# ATmega64M1_Dev_Board.net
KiCad netlist of a schematic drawn in EAGLE
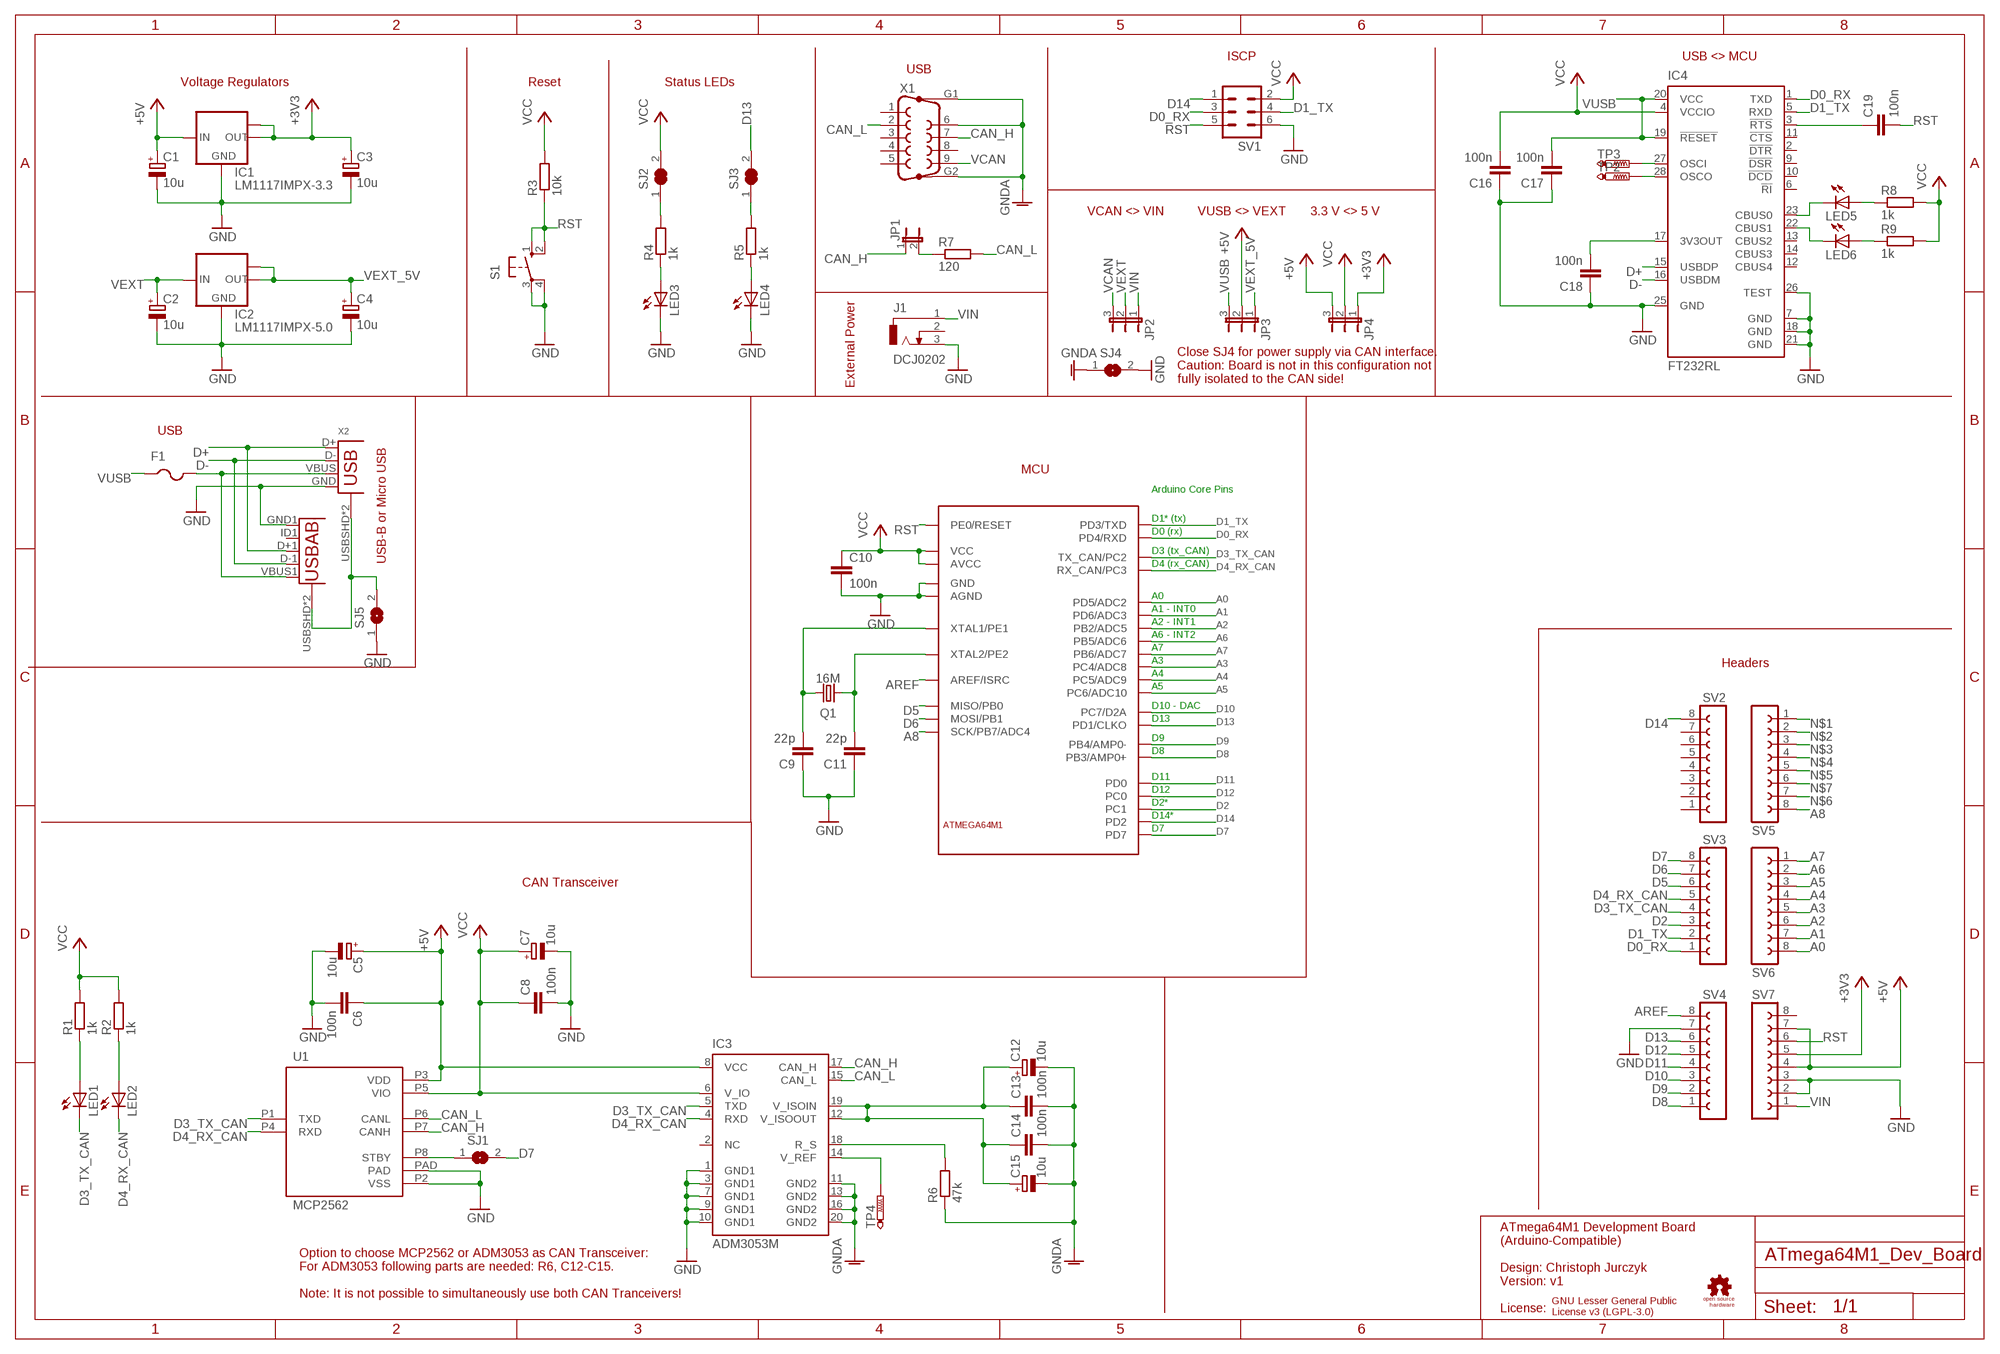
[diagram p0: schematic, sheet 1]

(export (version "E")
  (design (tool "Eeschema 10.0.6"))
  (components
    (comp (ref "C1")
      (value "10u")
      (footprint "eagle-import:A_3216-18W")
      (libsource (lib "eagle-import") (part "CPOL-EUA/3216-18W"))
    )
    (comp (ref "C2")
      (value "10u")
      (footprint "eagle-import:A_3216-18W")
      (libsource (lib "eagle-import") (part "CPOL-EUA/3216-18W"))
    )
    (comp (ref "C3")
      (value "10u")
      (footprint "eagle-import:A_3216-18W")
      (libsource (lib "eagle-import") (part "CPOL-EUA/3216-18W"))
    )
    (comp (ref "C4")
      (value "10u")
      (footprint "eagle-import:A_3216-18W")
      (libsource (lib "eagle-import") (part "CPOL-EUA/3216-18W"))
    )
    (comp (ref "C5")
      (value "10u")
      (footprint "eagle-import:A_3216-18W")
      (libsource (lib "eagle-import") (part "CPOL-EUA/3216-18W"))
    )
    (comp (ref "C6")
      (value "100n")
      (footprint "eagle-import:C0603")
      (libsource (lib "eagle-import") (part "C-EUC0603"))
    )
    (comp (ref "C7")
      (value "10u")
      (footprint "eagle-import:A_3216-18W")
      (libsource (lib "eagle-import") (part "CPOL-EUA/3216-18W"))
    )
    (comp (ref "C8")
      (value "100n")
      (footprint "eagle-import:C0603")
      (libsource (lib "eagle-import") (part "C-EUC0603"))
    )
    (comp (ref "C9")
      (value "22p")
      (footprint "eagle-import:C0603")
      (libsource (lib "eagle-import") (part "C-EUC0603"))
    )
    (comp (ref "C10")
      (value "100n")
      (footprint "eagle-import:C0603")
      (libsource (lib "eagle-import") (part "C-EUC0603"))
    )
    (comp (ref "C11")
      (value "22p")
      (footprint "eagle-import:C0603")
      (libsource (lib "eagle-import") (part "C-EUC0603"))
    )
    (comp (ref "C12")
      (value "10u")
      (footprint "eagle-import:A_3216-18W")
      (libsource (lib "eagle-import") (part "CPOL-EUA/3216-18W"))
    )
    (comp (ref "C13")
      (value "100n")
      (footprint "eagle-import:C0603")
      (libsource (lib "eagle-import") (part "C-EUC0603"))
    )
    (comp (ref "C14")
      (value "100n")
      (footprint "eagle-import:C0603")
      (libsource (lib "eagle-import") (part "C-EUC0603"))
    )
    (comp (ref "C15")
      (value "10u")
      (footprint "eagle-import:A_3216-18W")
      (libsource (lib "eagle-import") (part "CPOL-EUA/3216-18W"))
    )
    (comp (ref "C16")
      (value "100n")
      (footprint "eagle-import:C0603")
      (libsource (lib "eagle-import") (part "C-EUC0603"))
    )
    (comp (ref "C17")
      (value "100n")
      (footprint "eagle-import:C0603")
      (libsource (lib "eagle-import") (part "C-EUC0603"))
    )
    (comp (ref "C18")
      (value "100n")
      (footprint "eagle-import:C0603")
      (libsource (lib "eagle-import") (part "C-EUC0603"))
    )
    (comp (ref "C19")
      (value "100n")
      (footprint "eagle-import:C0603")
      (libsource (lib "eagle-import") (part "C-EUC0603"))
    )
    (comp (ref "F1")
      (value "PTCFUSE-1206")
      (footprint "eagle-import:R1206")
      (libsource (lib "eagle-import") (part "PTCFUSE-1206"))
    )
    (comp (ref "GOLD_ORB_SM1")
      (value "OSHWLOGOLOGO8MM")
      (footprint "eagle-import:OSHW_8MM")
      (libsource (lib "eagle-import") (part "OSHWLOGOLOGO8MM"))
    )
    (comp (ref "IC1")
      (value "LM1117IMPX-3.3")
      (footprint "eagle-import:SOT223")
      (libsource (lib "eagle-import") (part "LM1117IMPX-3.3"))
    )
    (comp (ref "IC2")
      (value "LM1117IMPX-5.0")
      (footprint "eagle-import:SOT223")
      (libsource (lib "eagle-import") (part "LM1117IMPX-5.0"))
    )
    (comp (ref "IC3")
      (value "ADM3053M")
      (footprint "eagle-import:SO20W")
      (libsource (lib "eagle-import") (part "ADM3053M"))
    )
    (comp (ref "IC4")
      (value "FT232RL")
      (footprint "eagle-import:SSOP28")
      (libsource (lib "eagle-import") (part "FT232RL"))
    )
    (comp (ref "IC11")
      (value "ATMEGA64M1TQFP32")
      (footprint "eagle-import:QFP-32")
      (libsource (lib "eagle-import") (part "ATMEGA64M1TQFP32"))
    )
    (comp (ref "J1")
      (value "DCJ0202")
      (footprint "eagle-import:DCJ0202")
      (libsource (lib "eagle-import") (part "DCJ0202"))
    )
    (comp (ref "JP1")
      (value "JP1E")
      (footprint "eagle-import:JP1")
      (libsource (lib "eagle-import") (part "JP1E"))
    )
    (comp (ref "JP2")
      (value "JP2E")
      (footprint "eagle-import:JP2")
      (libsource (lib "eagle-import") (part "JP2E"))
    )
    (comp (ref "JP3")
      (value "JP2E")
      (footprint "eagle-import:JP2")
      (libsource (lib "eagle-import") (part "JP2E"))
    )
    (comp (ref "JP4")
      (value "JP2E")
      (footprint "eagle-import:JP2")
      (libsource (lib "eagle-import") (part "JP2E"))
    )
    (comp (ref "LED1")
      (value "LEDSML0805")
      (footprint "eagle-import:SML0805")
      (libsource (lib "eagle-import") (part "LEDSML0805"))
    )
    (comp (ref "LED2")
      (value "LEDSML0805")
      (footprint "eagle-import:SML0805")
      (libsource (lib "eagle-import") (part "LEDSML0805"))
    )
    (comp (ref "LED3")
      (value "LEDSML0805")
      (footprint "eagle-import:SML0805")
      (libsource (lib "eagle-import") (part "LEDSML0805"))
    )
    (comp (ref "LED4")
      (value "LEDSML0805")
      (footprint "eagle-import:SML0805")
      (libsource (lib "eagle-import") (part "LEDSML0805"))
    )
    (comp (ref "LED5")
      (value "LEDSML0805")
      (footprint "eagle-import:SML0805")
      (libsource (lib "eagle-import") (part "LEDSML0805"))
    )
    (comp (ref "LED6")
      (value "LEDSML0805")
      (footprint "eagle-import:SML0805")
      (libsource (lib "eagle-import") (part "LEDSML0805"))
    )
    (comp (ref "Q1")
      (value "16M")
      (footprint "eagle-import:HC49_S")
      (libsource (lib "eagle-import") (part "CRYSTALHC49S"))
    )
    (comp (ref "R1")
      (value "1k")
      (footprint "eagle-import:M0805")
      (libsource (lib "eagle-import") (part "R-EU_M0805"))
    )
    (comp (ref "R2")
      (value "1k")
      (footprint "eagle-import:M0805")
      (libsource (lib "eagle-import") (part "R-EU_M0805"))
    )
    (comp (ref "R3")
      (value "10k")
      (footprint "eagle-import:M0805")
      (libsource (lib "eagle-import") (part "R-EU_M0805"))
    )
    (comp (ref "R4")
      (value "1k")
      (footprint "eagle-import:M0805")
      (libsource (lib "eagle-import") (part "R-EU_M0805"))
    )
    (comp (ref "R5")
      (value "1k")
      (footprint "eagle-import:M0805")
      (libsource (lib "eagle-import") (part "R-EU_M0805"))
    )
    (comp (ref "R6")
      (value "47k")
      (footprint "eagle-import:M0805")
      (libsource (lib "eagle-import") (part "R-EU_M0805"))
    )
    (comp (ref "R7")
      (value "120")
      (footprint "eagle-import:M0805")
      (libsource (lib "eagle-import") (part "R-EU_M0805"))
    )
    (comp (ref "R8")
      (value "1k")
      (footprint "eagle-import:M0805")
      (libsource (lib "eagle-import") (part "R-EU_M0805"))
    )
    (comp (ref "R9")
      (value "1k")
      (footprint "eagle-import:M0805")
      (libsource (lib "eagle-import") (part "R-EU_M0805"))
    )
    (comp (ref "S1")
      (value "10-XX")
      (footprint "eagle-import:B3F-10XX")
      (fields (field (name "MPN") "B3F-1000"))
      (libsource (lib "eagle-import") (part "10-XX"))
    )
    (comp (ref "SJ1") (value "SJ") (footprint "eagle-import:SJ") (libsource (lib "eagle-import") (part "SJ")))
    (comp (ref "SJ2")
      (value "SJ_NC")
      (footprint "eagle-import:SJ_NC")
      (libsource (lib "eagle-import") (part "SJ_NC"))
    )
    (comp (ref "SJ3")
      (value "SJ_NC")
      (footprint "eagle-import:SJ_NC")
      (libsource (lib "eagle-import") (part "SJ_NC"))
    )
    (comp (ref "SJ4") (value "SJ") (footprint "eagle-import:SJ") (libsource (lib "eagle-import") (part "SJ")))
    (comp (ref "SJ5") (value "SJ") (footprint "eagle-import:SJ") (libsource (lib "eagle-import") (part "SJ")))
    (comp (ref "SV1")
      (value "ML6")
      (footprint "eagle-import:ML6")
      (libsource (lib "eagle-import") (part "ML6"))
    )
    (comp (ref "SV2")
      (value "FE08-1")
      (footprint "eagle-import:FE08")
      (libsource (lib "eagle-import") (part "FE08-1"))
    )
    (comp (ref "SV3")
      (value "FE08-1")
      (footprint "eagle-import:FE08")
      (libsource (lib "eagle-import") (part "FE08-1"))
    )
    (comp (ref "SV4")
      (value "FE08-1")
      (footprint "eagle-import:FE08")
      (libsource (lib "eagle-import") (part "FE08-1"))
    )
    (comp (ref "SV5")
      (value "FE08-1")
      (footprint "eagle-import:FE08")
      (libsource (lib "eagle-import") (part "FE08-1"))
    )
    (comp (ref "SV6")
      (value "FE08-1")
      (footprint "eagle-import:FE08")
      (libsource (lib "eagle-import") (part "FE08-1"))
    )
    (comp (ref "SV7")
      (value "FE08-1")
      (footprint "eagle-import:FE08")
      (libsource (lib "eagle-import") (part "FE08-1"))
    )
    (comp (ref "TP2")
      (value "PTR1B1,27")
      (footprint "eagle-import:B1,27")
      (libsource (lib "eagle-import") (part "PTR1B1,27"))
    )
    (comp (ref "TP3")
      (value "PTR1B1,27")
      (footprint "eagle-import:B1,27")
      (libsource (lib "eagle-import") (part "PTR1B1,27"))
    )
    (comp (ref "TP4")
      (value "PTR1B1,27")
      (footprint "eagle-import:B1,27")
      (libsource (lib "eagle-import") (part "PTR1B1,27"))
    )
    (comp (ref "U1")
      (value "MCP2562")
      (footprint "eagle-import:DFN3X3")
      (libsource (lib "eagle-import") (part "MCP2562"))
    )
    (comp (ref "U2")
      (value "USB")
      (footprint "eagle-import:USB-MICRO-SMD_WITHOUT_PASTE")
      (libsource (lib "eagle-import") (part "USB"))
    )
    (comp (ref "X1")
      (value "F09HP")
      (footprint "eagle-import:F09HP")
      (libsource (lib "eagle-import") (part "F09HP"))
    )
    (comp (ref "X2")
      (value "USB-B-H")
      (footprint "eagle-import:USB-B-H")
      (libsource (lib "eagle-import") (part "USB-B-H"))
    )
  )
  (nets
    (net (code "1") (name "+3V3") (class "Default")
      (node (ref "C3") (pin "+") (pinfunction "+_+") (pintype "passive"))
      (node (ref "IC1") (pin "2") (pinfunction "OUT_2") (pintype "passive"))
      (node (ref "IC1") (pin "TAB") (pinfunction "OUT1_TAB") (pintype "passive"))
      (node (ref "JP4") (pin "1") (pinfunction "1_1") (pintype "passive"))
      (node (ref "SV7") (pin "5") (pinfunction "5_5") (pintype "passive"))
    )
    (net (code "2") (name "+5V") (class "Default")
      (node (ref "C1") (pin "+") (pinfunction "+_+") (pintype "passive"))
      (node (ref "C5") (pin "+") (pinfunction "+_+") (pintype "passive"))
      (node (ref "C6") (pin "1") (pinfunction "1_1") (pintype "passive"))
      (node (ref "IC1") (pin "3") (pinfunction "IN_3") (pintype "input"))
      (node (ref "IC3") (pin "8") (pinfunction "VCC_8") (pintype "power_in"))
      (node (ref "JP3") (pin "2") (pinfunction "2_2") (pintype "passive"))
      (node (ref "JP4") (pin "3") (pinfunction "3_3") (pintype "passive"))
      (node (ref "SV7") (pin "4") (pinfunction "4_4") (pintype "passive"))
      (node (ref "SV7") (pin "7") (pinfunction "7_7") (pintype "passive"))
      (node (ref "U1") (pin "P3") (pinfunction "VDD_P3") (pintype "bidirectional"))
    )
    (net (code "3") (name "/A0") (class "Default")
      (node (ref "IC11") (pin "13") (pinfunction "PD5/ADC2_13") (pintype "bidirectional"))
      (node (ref "SV6") (pin "8") (pinfunction "8_8") (pintype "passive"))
    )
    (net (code "4") (name "/A1") (class "Default")
      (node (ref "IC11") (pin "14") (pinfunction "PD6/ADC3_14") (pintype "bidirectional"))
      (node (ref "SV6") (pin "7") (pinfunction "7_7") (pintype "passive"))
    )
    (net (code "5") (name "/A2") (class "Default")
      (node (ref "IC11") (pin "16") (pinfunction "PB2/ADC5_16") (pintype "bidirectional"))
      (node (ref "SV6") (pin "6") (pinfunction "6_6") (pintype "passive"))
    )
    (net (code "6") (name "/A3") (class "Default")
      (node (ref "IC11") (pin "17") (pinfunction "PC4/ADC8_17") (pintype "bidirectional"))
      (node (ref "SV6") (pin "5") (pinfunction "5_5") (pintype "passive"))
    )
    (net (code "7") (name "/A4") (class "Default")
      (node (ref "IC11") (pin "18") (pinfunction "PC5/ADC9_18") (pintype "bidirectional"))
      (node (ref "SV6") (pin "4") (pinfunction "4_4") (pintype "passive"))
    )
    (net (code "8") (name "/A5") (class "Default")
      (node (ref "IC11") (pin "22") (pinfunction "PC6/ADC10_22") (pintype "bidirectional"))
      (node (ref "SV6") (pin "3") (pinfunction "3_3") (pintype "passive"))
    )
    (net (code "9") (name "/A6") (class "Default")
      (node (ref "IC11") (pin "26") (pinfunction "PB5/ADC6_26") (pintype "bidirectional"))
      (node (ref "SV6") (pin "2") (pinfunction "2_2") (pintype "passive"))
    )
    (net (code "10") (name "/A7") (class "Default")
      (node (ref "IC11") (pin "27") (pinfunction "PB6/ADC7_27") (pintype "bidirectional"))
      (node (ref "SV6") (pin "1") (pinfunction "1_1") (pintype "passive"))
    )
    (net (code "11") (name "/A8") (class "Default")
      (node (ref "IC11") (pin "28") (pinfunction "SCK/PB7/ADC4_28") (pintype "bidirectional"))
      (node (ref "SV5") (pin "8") (pinfunction "8_8") (pintype "passive"))
    )
    (net (code "12") (name "/AREF") (class "Default")
      (node (ref "IC11") (pin "21") (pinfunction "AREF/ISRC_21") (pintype "bidirectional"))
      (node (ref "SV4") (pin "8") (pinfunction "8_8") (pintype "passive"))
    )
    (net (code "13") (name "/CAN_H") (class "Default")
      (node (ref "IC3") (pin "17") (pinfunction "CAN_H_17") (pintype "bidirectional"))
      (node (ref "JP1") (pin "1") (pinfunction "1_1") (pintype "passive"))
      (node (ref "U1") (pin "P7") (pinfunction "CANH_P7") (pintype "bidirectional"))
      (node (ref "X1") (pin "7") (pinfunction "7_7") (pintype "passive"))
    )
    (net (code "14") (name "/CAN_L") (class "Default")
      (node (ref "IC3") (pin "15") (pinfunction "CAN_L_15") (pintype "bidirectional"))
      (node (ref "R7") (pin "2") (pinfunction "2_2") (pintype "passive"))
      (node (ref "U1") (pin "P6") (pinfunction "CANL_P6") (pintype "bidirectional"))
      (node (ref "X1") (pin "2") (pinfunction "2_2") (pintype "passive"))
    )
    (net (code "15") (name "/D+") (class "Default")
      (node (ref "IC4") (pin "15") (pinfunction "USBDP_15") (pintype "bidirectional"))
      (node (ref "U2") (pin "D+1") (pinfunction "D+_D+1") (pintype "bidirectional"))
      (node (ref "X2") (pin "D+") (pinfunction "D+_D+") (pintype "bidirectional"))
    )
    (net (code "16") (name "/D-") (class "Default")
      (node (ref "IC4") (pin "16") (pinfunction "USBDM_16") (pintype "bidirectional"))
      (node (ref "U2") (pin "D-1") (pinfunction "D-_D-1") (pintype "bidirectional"))
      (node (ref "X2") (pin "D-") (pinfunction "D-_D-") (pintype "bidirectional"))
    )
    (net (code "17") (name "/D0_RX") (class "Default")
      (node (ref "IC11") (pin "12") (pinfunction "PD4/RXD_12") (pintype "bidirectional"))
      (node (ref "IC4") (pin "1") (pinfunction "TXD_1") (pintype "output"))
      (node (ref "SV1") (pin "3") (pinfunction "3_3") (pintype "passive"))
      (node (ref "SV3") (pin "1") (pinfunction "1_1") (pintype "passive"))
    )
    (net (code "18") (name "/D1_TX") (class "Default")
      (node (ref "IC11") (pin "2") (pinfunction "PD3/TXD_2") (pintype "bidirectional"))
      (node (ref "IC4") (pin "5") (pinfunction "RXD_5") (pintype "input"))
      (node (ref "SV1") (pin "4") (pinfunction "4_4") (pintype "passive"))
      (node (ref "SV3") (pin "2") (pinfunction "2_2") (pintype "passive"))
    )
    (net (code "19") (name "/D2") (class "Default")
      (node (ref "IC11") (pin "3") (pinfunction "PC1_3") (pintype "bidirectional"))
      (node (ref "SV3") (pin "3") (pinfunction "3_3") (pintype "passive"))
    )
    (net (code "20") (name "/D3_TX_CAN") (class "Default")
      (node (ref "IC11") (pin "6") (pinfunction "TX_CAN/PC2_6") (pintype "bidirectional"))
      (node (ref "IC3") (pin "5") (pinfunction "TXD_5") (pintype "input"))
      (node (ref "LED1") (pin "C") (pinfunction "C_C") (pintype "passive"))
      (node (ref "SV3") (pin "4") (pinfunction "4_4") (pintype "passive"))
      (node (ref "U1") (pin "P1") (pinfunction "TXD_P1") (pintype "bidirectional"))
    )
    (net (code "21") (name "/D4_RX_CAN") (class "Default")
      (node (ref "IC11") (pin "7") (pinfunction "RX_CAN/PC3_7") (pintype "bidirectional"))
      (node (ref "IC3") (pin "4") (pinfunction "RXD_4") (pintype "output"))
      (node (ref "LED2") (pin "C") (pinfunction "C_C") (pintype "passive"))
      (node (ref "SV3") (pin "5") (pinfunction "5_5") (pintype "passive"))
      (node (ref "U1") (pin "P4") (pinfunction "RXD_P4") (pintype "bidirectional"))
    )
    (net (code "22") (name "/D5") (class "Default")
      (node (ref "IC11") (pin "8") (pinfunction "MISO/PB0_8") (pintype "bidirectional"))
      (node (ref "SV3") (pin "6") (pinfunction "6_6") (pintype "passive"))
    )
    (net (code "23") (name "/D6") (class "Default")
      (node (ref "IC11") (pin "9") (pinfunction "MOSI/PB1_9") (pintype "bidirectional"))
      (node (ref "SV3") (pin "7") (pinfunction "7_7") (pintype "passive"))
    )
    (net (code "24") (name "/D7") (class "Default")
      (node (ref "IC11") (pin "15") (pinfunction "PD7_15") (pintype "bidirectional"))
      (node (ref "SJ1") (pin "2") (pinfunction "2_2") (pintype "passive"))
      (node (ref "SV3") (pin "8") (pinfunction "8_8") (pintype "passive"))
    )
    (net (code "25") (name "/D8") (class "Default")
      (node (ref "IC11") (pin "23") (pinfunction "PB3/AMP0+_23") (pintype "bidirectional"))
      (node (ref "SV4") (pin "1") (pinfunction "1_1") (pintype "passive"))
    )
    (net (code "26") (name "/D9") (class "Default")
      (node (ref "IC11") (pin "24") (pinfunction "PB4/AMP0-_24") (pintype "bidirectional"))
      (node (ref "SV4") (pin "2") (pinfunction "2_2") (pintype "passive"))
    )
    (net (code "27") (name "/D10") (class "Default")
      (node (ref "IC11") (pin "25") (pinfunction "PC7/D2A_25") (pintype "bidirectional"))
      (node (ref "SV4") (pin "3") (pinfunction "3_3") (pintype "passive"))
    )
    (net (code "28") (name "/D11") (class "Default")
      (node (ref "IC11") (pin "29") (pinfunction "PD0_29") (pintype "bidirectional"))
      (node (ref "SV4") (pin "4") (pinfunction "4_4") (pintype "passive"))
    )
    (net (code "29") (name "/D12") (class "Default")
      (node (ref "IC11") (pin "30") (pinfunction "PC0_30") (pintype "bidirectional"))
      (node (ref "SV4") (pin "5") (pinfunction "5_5") (pintype "passive"))
    )
    (net (code "30") (name "/D13") (class "Default")
      (node (ref "IC11") (pin "32") (pinfunction "PD1/CLKO_32") (pintype "bidirectional"))
      (node (ref "SJ3") (pin "2") (pinfunction "2_2") (pintype "passive"))
      (node (ref "SV4") (pin "6") (pinfunction "6_6") (pintype "passive"))
    )
    (net (code "31") (name "/D14") (class "Default")
      (node (ref "IC11") (pin "1") (pinfunction "PD2_1") (pintype "bidirectional"))
      (node (ref "SV1") (pin "1") (pinfunction "1_1") (pintype "passive"))
      (node (ref "SV2") (pin "8") (pinfunction "8_8") (pintype "passive"))
    )
    (net (code "32") (name "/N$1") (class "Default")
      (node (ref "SV5") (pin "1") (pinfunction "1_1") (pintype "passive"))
    )
    (net (code "33") (name "/N$2") (class "Default")
      (node (ref "SV5") (pin "2") (pinfunction "2_2") (pintype "passive"))
    )
    (net (code "34") (name "/N$3") (class "Default")
      (node (ref "SV5") (pin "3") (pinfunction "3_3") (pintype "passive"))
    )
    (net (code "35") (name "/N$4") (class "Default")
      (node (ref "SV5") (pin "4") (pinfunction "4_4") (pintype "passive"))
    )
    (net (code "36") (name "/N$5") (class "Default")
      (node (ref "SV5") (pin "5") (pinfunction "5_5") (pintype "passive"))
    )
    (net (code "37") (name "/N$6") (class "Default")
      (node (ref "SV5") (pin "7") (pinfunction "7_7") (pintype "passive"))
    )
    (net (code "38") (name "/N$7") (class "Default")
      (node (ref "SV5") (pin "6") (pinfunction "6_6") (pintype "passive"))
    )
    (net (code "39") (name "/RST") (class "Default")
      (node (ref "C19") (pin "2") (pinfunction "2_2") (pintype "passive"))
      (node (ref "IC11") (pin "31") (pinfunction "PE0/RESET_31") (pintype "bidirectional"))
      (node (ref "R3") (pin "1") (pinfunction "1_1") (pintype "passive"))
      (node (ref "S1") (pin "1") (pinfunction "S_1") (pintype "passive"))
      (node (ref "S1") (pin "2") (pinfunction "S1_2") (pintype "passive"))
      (node (ref "SV1") (pin "5") (pinfunction "5_5") (pintype "passive"))
      (node (ref "SV7") (pin "6") (pinfunction "6_6") (pintype "passive"))
    )
    (net (code "40") (name "/VCAN") (class "Default")
      (node (ref "JP2") (pin "3") (pinfunction "3_3") (pintype "passive"))
      (node (ref "X1") (pin "9") (pinfunction "9_9") (pintype "passive"))
    )
    (net (code "41") (name "/VEXT") (class "Default")
      (node (ref "C2") (pin "+") (pinfunction "+_+") (pintype "passive"))
      (node (ref "IC2") (pin "3") (pinfunction "IN_3") (pintype "input"))
      (node (ref "JP2") (pin "2") (pinfunction "2_2") (pintype "passive"))
    )
    (net (code "42") (name "/VEXT_5V") (class "Default")
      (node (ref "C4") (pin "+") (pinfunction "+_+") (pintype "passive"))
      (node (ref "IC2") (pin "2") (pinfunction "OUT_2") (pintype "passive"))
      (node (ref "IC2") (pin "TAB") (pinfunction "OUT1_TAB") (pintype "passive"))
      (node (ref "JP3") (pin "1") (pinfunction "1_1") (pintype "passive"))
    )
    (net (code "43") (name "/VIN") (class "Default")
      (node (ref "J1") (pin "1") (pinfunction "1_1") (pintype "passive"))
      (node (ref "JP2") (pin "1") (pinfunction "1_1") (pintype "passive"))
      (node (ref "SV7") (pin "1") (pinfunction "1_1") (pintype "passive"))
    )
    (net (code "44") (name "/VUSB") (class "Default")
      (node (ref "C17") (pin "2") (pinfunction "2_2") (pintype "passive"))
      (node (ref "F1") (pin "1") (pinfunction "1_1") (pintype "passive"))
      (node (ref "IC4") (pin "19") (pinfunction "~{RESET}_19") (pintype "input"))
      (node (ref "IC4") (pin "20") (pinfunction "VCC_20") (pintype "power_in"))
      (node (ref "JP3") (pin "3") (pinfunction "3_3") (pintype "passive"))
    )
    (net (code "45") (name "GND") (class "Default")
      (node (ref "C1") (pin "-") (pinfunction "-_-") (pintype "passive"))
      (node (ref "C10") (pin "2") (pinfunction "2_2") (pintype "passive"))
      (node (ref "C11") (pin "1") (pinfunction "1_1") (pintype "passive"))
      (node (ref "C16") (pin "1") (pinfunction "1_1") (pintype "passive"))
      (node (ref "C17") (pin "1") (pinfunction "1_1") (pintype "passive"))
      (node (ref "C18") (pin "1") (pinfunction "1_1") (pintype "passive"))
      (node (ref "C2") (pin "-") (pinfunction "-_-") (pintype "passive"))
      (node (ref "C3") (pin "-") (pinfunction "-_-") (pintype "passive"))
      (node (ref "C4") (pin "-") (pinfunction "-_-") (pintype "passive"))
      (node (ref "C5") (pin "-") (pinfunction "-_-") (pintype "passive"))
      (node (ref "C6") (pin "2") (pinfunction "2_2") (pintype "passive"))
      (node (ref "C7") (pin "-") (pinfunction "-_-") (pintype "passive"))
      (node (ref "C8") (pin "2") (pinfunction "2_2") (pintype "passive"))
      (node (ref "C9") (pin "1") (pinfunction "1_1") (pintype "passive"))
      (node (ref "IC1") (pin "1") (pinfunction "GND_1") (pintype "input"))
      (node (ref "IC11") (pin "20") (pinfunction "AGND_20") (pintype "bidirectional"))
      (node (ref "IC11") (pin "5") (pinfunction "GND_5") (pintype "bidirectional"))
      (node (ref "IC2") (pin "1") (pinfunction "GND_1") (pintype "input"))
      (node (ref "IC3") (pin "1") (pinfunction "GND1_1") (pintype "power_in"))
      (node (ref "IC3") (pin "10") (pinfunction "GND1_10") (pintype "power_in"))
      (node (ref "IC3") (pin "3") (pinfunction "GND1_3") (pintype "power_in"))
      (node (ref "IC3") (pin "7") (pinfunction "GND1_7") (pintype "power_in"))
      (node (ref "IC3") (pin "9") (pinfunction "GND1_9") (pintype "power_in"))
      (node (ref "IC4") (pin "18") (pinfunction "GND_18") (pintype "power_in"))
      (node (ref "IC4") (pin "21") (pinfunction "GND_21") (pintype "power_in"))
      (node (ref "IC4") (pin "25") (pinfunction "GND_25") (pintype "power_in"))
      (node (ref "IC4") (pin "26") (pinfunction "TEST_26") (pintype "input"))
      (node (ref "IC4") (pin "7") (pinfunction "GND_7") (pintype "power_in"))
      (node (ref "J1") (pin "3") (pinfunction "3_3") (pintype "passive"))
      (node (ref "LED3") (pin "C") (pinfunction "C_C") (pintype "passive"))
      (node (ref "LED4") (pin "C") (pinfunction "C_C") (pintype "passive"))
      (node (ref "S1") (pin "3") (pinfunction "P_3") (pintype "passive"))
      (node (ref "S1") (pin "4") (pinfunction "P1_4") (pintype "passive"))
      (node (ref "SJ4") (pin "2") (pinfunction "2_2") (pintype "passive"))
      (node (ref "SJ5") (pin "1") (pinfunction "1_1") (pintype "passive"))
      (node (ref "SV1") (pin "6") (pinfunction "6_6") (pintype "passive"))
      (node (ref "SV4") (pin "7") (pinfunction "7_7") (pintype "passive"))
      (node (ref "SV7") (pin "2") (pinfunction "2_2") (pintype "passive"))
      (node (ref "SV7") (pin "3") (pinfunction "3_3") (pintype "passive"))
      (node (ref "U1") (pin "P2") (pinfunction "VSS_P2") (pintype "bidirectional"))
      (node (ref "U1") (pin "PAD") (pinfunction "PAD_PAD") (pintype "bidirectional"))
      (node (ref "U2") (pin "GND1") (pinfunction "GND_GND1") (pintype "bidirectional"))
      (node (ref "X2") (pin "GND") (pinfunction "GND_GND") (pintype "bidirectional"))
    )
    (net (code "46") (name "GNDA") (class "Default")
      (node (ref "C12") (pin "-") (pinfunction "-_-") (pintype "passive"))
      (node (ref "C13") (pin "2") (pinfunction "2_2") (pintype "passive"))
      (node (ref "C14") (pin "2") (pinfunction "2_2") (pintype "passive"))
      (node (ref "C15") (pin "-") (pinfunction "-_-") (pintype "passive"))
      (node (ref "IC3") (pin "11") (pinfunction "GND2_11") (pintype "power_in"))
      (node (ref "IC3") (pin "13") (pinfunction "GND2_13") (pintype "power_in"))
      (node (ref "IC3") (pin "16") (pinfunction "GND2_16") (pintype "power_in"))
      (node (ref "IC3") (pin "20") (pinfunction "GND2_20") (pintype "power_in"))
      (node (ref "R6") (pin "1") (pinfunction "1_1") (pintype "passive"))
      (node (ref "SJ4") (pin "1") (pinfunction "1_1") (pintype "passive"))
      (node (ref "X1") (pin "6") (pinfunction "6_6") (pintype "passive"))
      (node (ref "X1") (pin "G1") (pinfunction "G1_G1") (pintype "passive"))
      (node (ref "X1") (pin "G2") (pinfunction "G2_G2") (pintype "passive"))
    )
    (net (code "47") (name "Net-(IC3-R_S)") (class "Default")
      (node (ref "IC3") (pin "18") (pinfunction "R_S_18") (pintype "passive"))
      (node (ref "R6") (pin "2") (pinfunction "2_2") (pintype "passive"))
    )
    (net (code "48") (name "Net-(IC3-V_ISOIN)") (class "Default")
      (node (ref "C12") (pin "+") (pinfunction "+_+") (pintype "passive"))
      (node (ref "C13") (pin "1") (pinfunction "1_1") (pintype "passive"))
      (node (ref "C14") (pin "1") (pinfunction "1_1") (pintype "passive"))
      (node (ref "C15") (pin "+") (pinfunction "+_+") (pintype "passive"))
      (node (ref "IC3") (pin "12") (pinfunction "V_ISOOUT_12") (pintype "output"))
      (node (ref "IC3") (pin "19") (pinfunction "V_ISOIN_19") (pintype "input"))
    )
    (net (code "49") (name "Net-(IC3-V_REF)") (class "Default")
      (node (ref "IC3") (pin "14") (pinfunction "V_REF_14") (pintype "output"))
      (node (ref "TP4") (pin "TP") (pinfunction "TP_TP") (pintype "input"))
    )
    (net (code "50") (name "Net-(IC4-3V3OUT)") (class "Default")
      (node (ref "C18") (pin "2") (pinfunction "2_2") (pintype "passive"))
      (node (ref "IC4") (pin "17") (pinfunction "3V3OUT_17") (pintype "output"))
    )
    (net (code "51") (name "Net-(IC4-CBUS0)") (class "Default")
      (node (ref "IC4") (pin "23") (pinfunction "CBUS0_23") (pintype "bidirectional"))
      (node (ref "LED5") (pin "C") (pinfunction "C_C") (pintype "passive"))
    )
    (net (code "52") (name "Net-(IC4-CBUS1)") (class "Default")
      (node (ref "IC4") (pin "22") (pinfunction "CBUS1_22") (pintype "bidirectional"))
      (node (ref "LED6") (pin "C") (pinfunction "C_C") (pintype "passive"))
    )
    (net (code "53") (name "Net-(IC4-OSCI)") (class "Default")
      (node (ref "IC4") (pin "27") (pinfunction "OSCI_27") (pintype "input"))
      (node (ref "TP3") (pin "TP") (pinfunction "TP_TP") (pintype "input"))
    )
    (net (code "54") (name "Net-(IC4-OSCO)") (class "Default")
      (node (ref "IC4") (pin "28") (pinfunction "OSCO_28") (pintype "output"))
      (node (ref "TP2") (pin "TP") (pinfunction "TP_TP") (pintype "input"))
    )
    (net (code "55") (name "Net-(IC4-~{RTS})") (class "Default")
      (node (ref "C19") (pin "1") (pinfunction "1_1") (pintype "passive"))
      (node (ref "IC4") (pin "3") (pinfunction "~{RTS}_3") (pintype "output"))
    )
    (net (code "56") (name "Net-(IC11-XTAL1{slash}PE1)") (class "Default")
      (node (ref "C9") (pin "2") (pinfunction "2_2") (pintype "passive"))
      (node (ref "IC11") (pin "10") (pinfunction "XTAL1/PE1_10") (pintype "bidirectional"))
      (node (ref "Q1") (pin "2") (pinfunction "2_2") (pintype "passive"))
    )
    (net (code "57") (name "Net-(IC11-XTAL2{slash}PE2)") (class "Default")
      (node (ref "C11") (pin "2") (pinfunction "2_2") (pintype "passive"))
      (node (ref "IC11") (pin "11") (pinfunction "XTAL2/PE2_11") (pintype "bidirectional"))
      (node (ref "Q1") (pin "1") (pinfunction "1_1") (pintype "passive"))
    )
    (net (code "58") (name "Net-(JP1-Pad2)") (class "Default")
      (node (ref "JP1") (pin "2") (pinfunction "2_2") (pintype "passive"))
      (node (ref "R7") (pin "1") (pinfunction "1_1") (pintype "passive"))
    )
    (net (code "59") (name "Net-(LED1-PadA)") (class "Default")
      (node (ref "LED1") (pin "A") (pinfunction "A_A") (pintype "passive"))
      (node (ref "R1") (pin "1") (pinfunction "1_1") (pintype "passive"))
    )
    (net (code "60") (name "Net-(LED2-PadA)") (class "Default")
      (node (ref "LED2") (pin "A") (pinfunction "A_A") (pintype "passive"))
      (node (ref "R2") (pin "1") (pinfunction "1_1") (pintype "passive"))
    )
    (net (code "61") (name "Net-(LED3-PadA)") (class "Default")
      (node (ref "LED3") (pin "A") (pinfunction "A_A") (pintype "passive"))
      (node (ref "R4") (pin "1") (pinfunction "1_1") (pintype "passive"))
    )
    (net (code "62") (name "Net-(LED4-PadA)") (class "Default")
      (node (ref "LED4") (pin "A") (pinfunction "A_A") (pintype "passive"))
      (node (ref "R5") (pin "1") (pinfunction "1_1") (pintype "passive"))
    )
    (net (code "63") (name "Net-(LED5-PadA)") (class "Default")
      (node (ref "LED5") (pin "A") (pinfunction "A_A") (pintype "passive"))
      (node (ref "R8") (pin "1") (pinfunction "1_1") (pintype "passive"))
    )
    (net (code "64") (name "Net-(LED6-PadA)") (class "Default")
      (node (ref "LED6") (pin "A") (pinfunction "A_A") (pintype "passive"))
      (node (ref "R9") (pin "1") (pinfunction "1_1") (pintype "passive"))
    )
    (net (code "65") (name "Net-(R4-Pad2)") (class "Default")
      (node (ref "R4") (pin "2") (pinfunction "2_2") (pintype "passive"))
      (node (ref "SJ2") (pin "1") (pinfunction "1_1") (pintype "passive"))
    )
    (net (code "66") (name "Net-(R5-Pad2)") (class "Default")
      (node (ref "R5") (pin "2") (pinfunction "2_2") (pintype "passive"))
      (node (ref "SJ3") (pin "1") (pinfunction "1_1") (pintype "passive"))
    )
    (net (code "67") (name "Net-(SJ5-Pad2)") (class "Default")
      (node (ref "SJ5") (pin "2") (pinfunction "2_2") (pintype "passive"))
      (node (ref "U2") (pin "USBSHD") (pinfunction "USBSHD_USBSHD") (pintype "bidirectional"))
      (node (ref "U2") (pin "USBSHD1") (pinfunction "USBSHD_USBSHD1") (pintype "bidirectional"))
      (node (ref "X2") (pin "USBSHD") (pinfunction "USBSHD_USBSHD") (pintype "bidirectional"))
      (node (ref "X2") (pin "USBSHD2") (pinfunction "USBSHD_USBSHD2") (pintype "bidirectional"))
    )
    (net (code "68") (name "Net-(U1-STBY)") (class "Default")
      (node (ref "SJ1") (pin "1") (pinfunction "1_1") (pintype "passive"))
      (node (ref "U1") (pin "P8") (pinfunction "STBY_P8") (pintype "bidirectional"))
    )
    (net (code "69") (name "Net-(U2-VBUS)") (class "Default")
      (node (ref "F1") (pin "2") (pinfunction "2_2") (pintype "passive"))
      (node (ref "U2") (pin "VBUS1") (pinfunction "VBUS_VBUS1") (pintype "bidirectional"))
      (node (ref "X2") (pin "VBUS") (pinfunction "VBUS_VBUS") (pintype "bidirectional"))
    )
    (net (code "70") (name "VCC") (class "Default")
      (node (ref "C10") (pin "1") (pinfunction "1_1") (pintype "passive"))
      (node (ref "C16") (pin "2") (pinfunction "2_2") (pintype "passive"))
      (node (ref "C7") (pin "+") (pinfunction "+_+") (pintype "passive"))
      (node (ref "C8") (pin "1") (pinfunction "1_1") (pintype "passive"))
      (node (ref "IC11") (pin "19") (pinfunction "AVCC_19") (pintype "bidirectional"))
      (node (ref "IC11") (pin "4") (pinfunction "VCC_4") (pintype "bidirectional"))
      (node (ref "IC3") (pin "6") (pinfunction "V_IO_6") (pintype "power_in"))
      (node (ref "IC4") (pin "4") (pinfunction "VCCIO_4") (pintype "power_in"))
      (node (ref "JP4") (pin "2") (pinfunction "2_2") (pintype "passive"))
      (node (ref "R1") (pin "2") (pinfunction "2_2") (pintype "passive"))
      (node (ref "R2") (pin "2") (pinfunction "2_2") (pintype "passive"))
      (node (ref "R3") (pin "2") (pinfunction "2_2") (pintype "passive"))
      (node (ref "R8") (pin "2") (pinfunction "2_2") (pintype "passive"))
      (node (ref "R9") (pin "2") (pinfunction "2_2") (pintype "passive"))
      (node (ref "SJ2") (pin "2") (pinfunction "2_2") (pintype "passive"))
      (node (ref "SV1") (pin "2") (pinfunction "2_2") (pintype "passive"))
      (node (ref "U1") (pin "P5") (pinfunction "VIO_P5") (pintype "bidirectional"))
    )
    (net (code "71") (name "unconnected-(IC3-NC-Pad2)") (class "Default")
      (node (ref "IC3") (pin "2") (pinfunction "NC_2") (pintype "no_connect"))
    )
    (net (code "72") (name "unconnected-(IC4-CBUS2-Pad13)") (class "Default")
      (node (ref "IC4") (pin "13") (pinfunction "CBUS2_13") (pintype "bidirectional"))
    )
    (net (code "73") (name "unconnected-(IC4-CBUS3-Pad14)") (class "Default")
      (node (ref "IC4") (pin "14") (pinfunction "CBUS3_14") (pintype "bidirectional"))
    )
    (net (code "74") (name "unconnected-(IC4-CBUS4-Pad12)") (class "Default")
      (node (ref "IC4") (pin "12") (pinfunction "CBUS4_12") (pintype "bidirectional"))
    )
    (net (code "75") (name "unconnected-(IC4-~{CTS}-Pad11)") (class "Default")
      (node (ref "IC4") (pin "11") (pinfunction "~{CTS}_11") (pintype "input"))
    )
    (net (code "76") (name "unconnected-(IC4-~{DCD}-Pad10)") (class "Default")
      (node (ref "IC4") (pin "10") (pinfunction "~{DCD}_10") (pintype "input"))
    )
    (net (code "77") (name "unconnected-(IC4-~{DSR}-Pad9)") (class "Default")
      (node (ref "IC4") (pin "9") (pinfunction "~{DSR}_9") (pintype "input"))
    )
    (net (code "78") (name "unconnected-(IC4-~{DTR}-Pad2)") (class "Default")
      (node (ref "IC4") (pin "2") (pinfunction "~{DTR}_2") (pintype "output"))
    )
    (net (code "79") (name "unconnected-(IC4-~{RI}-Pad6)") (class "Default")
      (node (ref "IC4") (pin "6") (pinfunction "~{RI}_6") (pintype "input"))
    )
    (net (code "80") (name "unconnected-(J1-Pad2)") (class "Default")
      (node (ref "J1") (pin "2") (pinfunction "2_2") (pintype "passive"))
    )
    (net (code "81") (name "unconnected-(SV2-Pad1)") (class "Default")
      (node (ref "SV2") (pin "1") (pinfunction "1_1") (pintype "passive"))
    )
    (net (code "82") (name "unconnected-(SV2-Pad2)") (class "Default")
      (node (ref "SV2") (pin "2") (pinfunction "2_2") (pintype "passive"))
    )
    (net (code "83") (name "unconnected-(SV2-Pad3)") (class "Default")
      (node (ref "SV2") (pin "3") (pinfunction "3_3") (pintype "passive"))
    )
    (net (code "84") (name "unconnected-(SV2-Pad4)") (class "Default")
      (node (ref "SV2") (pin "4") (pinfunction "4_4") (pintype "passive"))
    )
    (net (code "85") (name "unconnected-(SV2-Pad5)") (class "Default")
      (node (ref "SV2") (pin "5") (pinfunction "5_5") (pintype "passive"))
    )
    (net (code "86") (name "unconnected-(SV2-Pad6)") (class "Default")
      (node (ref "SV2") (pin "6") (pinfunction "6_6") (pintype "passive"))
    )
    (net (code "87") (name "unconnected-(SV2-Pad7)") (class "Default")
      (node (ref "SV2") (pin "7") (pinfunction "7_7") (pintype "passive"))
    )
    (net (code "88") (name "unconnected-(SV7-Pad8)") (class "Default")
      (node (ref "SV7") (pin "8") (pinfunction "8_8") (pintype "passive"))
    )
    (net (code "89") (name "unconnected-(U2-USBID-PadID1)") (class "Default")
      (node (ref "U2") (pin "ID1") (pinfunction "USBID_ID1") (pintype "bidirectional"))
    )
    (net (code "90") (name "unconnected-(X1-Pad1)") (class "Default")
      (node (ref "X1") (pin "1") (pinfunction "1_1") (pintype "passive"))
    )
    (net (code "91") (name "unconnected-(X1-Pad3)") (class "Default")
      (node (ref "X1") (pin "3") (pinfunction "3_3") (pintype "passive"))
    )
    (net (code "92") (name "unconnected-(X1-Pad4)") (class "Default")
      (node (ref "X1") (pin "4") (pinfunction "4_4") (pintype "passive"))
    )
    (net (code "93") (name "unconnected-(X1-Pad5)") (class "Default")
      (node (ref "X1") (pin "5") (pinfunction "5_5") (pintype "passive"))
    )
    (net (code "94") (name "unconnected-(X1-Pad8)") (class "Default")
      (node (ref "X1") (pin "8") (pinfunction "8_8") (pintype "passive"))
    )
  )
)
